# LEDMiniCube_AAmp.net
KiCad netlist of a schematic drawn in Altium Designer
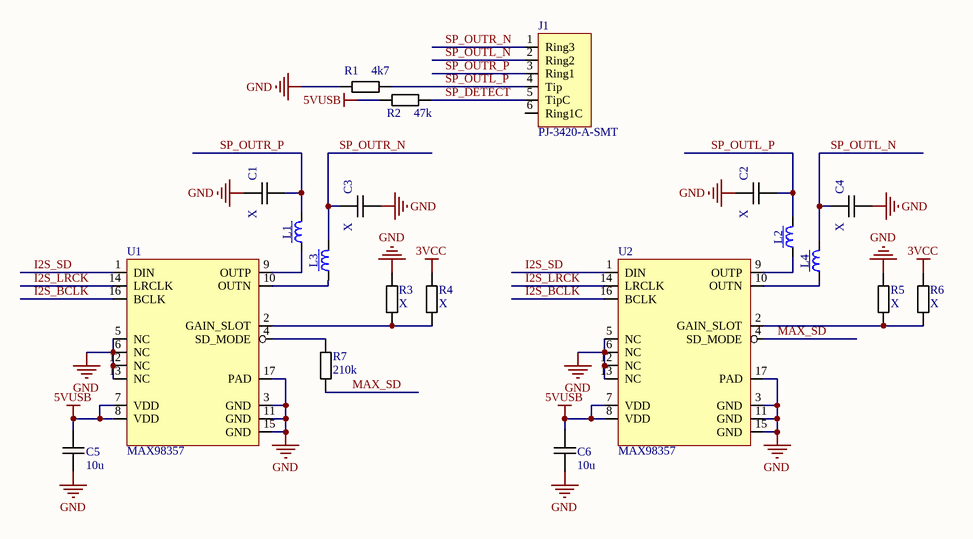
[diagram p0: LEDMiniCube_AAmp.SchDoc]

(export (version "E")
  (design (tool "Eeschema 10.0.6"))
  (components
    (comp (ref "C1") (value "X") (footprint "CAPC2012L") (libsource (lib "BMFT_lib") (part "Capacitor")))
    (comp (ref "C2") (value "X") (footprint "CAPC2012L") (libsource (lib "BMFT_lib") (part "Capacitor")))
    (comp (ref "C3") (value "X") (footprint "CAPC2012L") (libsource (lib "BMFT_lib") (part "Capacitor")))
    (comp (ref "C4") (value "X") (footprint "CAPC2012L") (libsource (lib "BMFT_lib") (part "Capacitor")))
    (comp (ref "C5") (value "10u") (footprint "CAPC2012L") (libsource (lib "BMFT_lib") (part "Capacitor")))
    (comp (ref "C6") (value "10u") (footprint "CAPC2012L") (libsource (lib "BMFT_lib") (part "Capacitor")))
    (comp (ref "J1")
      (value "PJ-3420-A-SMT")
      (footprint "PJ-3420-A-SMT")
      (libsource (lib "BMFT_lib") (part "3.5 socket PJ-3420-A-SMT"))
    )
    (comp (ref "L1")
      (value "~")
      (footprint "INDC2012L")
      (description "Inductor With Core")
      (fields (field (name "AUTHOR") "CERN DEM JLC"))
      (libsource (lib "Inductors & Transformers") (part "Inductor With Magnetic core"))
    )
    (comp (ref "L2")
      (value "~")
      (footprint "INDC2012L")
      (description "Inductor With Core")
      (fields (field (name "AUTHOR") "CERN DEM JLC"))
      (libsource (lib "Inductors & Transformers") (part "Inductor With Magnetic core"))
    )
    (comp (ref "L3")
      (value "~")
      (footprint "INDC2012L")
      (description "Inductor With Core")
      (fields (field (name "AUTHOR") "CERN DEM JLC"))
      (libsource (lib "Inductors & Transformers") (part "Inductor With Magnetic core"))
    )
    (comp (ref "L4")
      (value "~")
      (footprint "INDC2012L")
      (description "Inductor With Core")
      (fields (field (name "AUTHOR") "CERN DEM JLC"))
      (libsource (lib "Inductors & Transformers") (part "Inductor With Magnetic core"))
    )
    (comp (ref "R1") (value "4k7") (footprint "RESC1608L") (libsource (lib "BMFT_lib") (part "Resistor")))
    (comp (ref "R2") (value "47k") (footprint "RESC1608L") (libsource (lib "BMFT_lib") (part "Resistor")))
    (comp (ref "R3") (value "X") (footprint "RESC1608L") (libsource (lib "BMFT_lib") (part "Resistor")))
    (comp (ref "R4") (value "X") (footprint "RESC1608L") (libsource (lib "BMFT_lib") (part "Resistor")))
    (comp (ref "R5") (value "X") (footprint "RESC1608L") (libsource (lib "BMFT_lib") (part "Resistor")))
    (comp (ref "R6") (value "X") (footprint "RESC1608L") (libsource (lib "BMFT_lib") (part "Resistor")))
    (comp (ref "R7") (value "210k") (footprint "RESC1608L") (libsource (lib "BMFT_lib") (part "Resistor")))
    (comp (ref "U1")
      (value "MAX98357")
      (footprint "PQFN50P300X300X80_HS-17N")
      (fields (field (name "PART") "MAX98357A"))
      (libsource (lib "BMFT_lib") (part "MAX98357"))
    )
    (comp (ref "U2")
      (value "MAX98357")
      (footprint "PQFN50P300X300X80_HS-17N")
      (fields (field (name "PART") "MAX98357A"))
      (libsource (lib "BMFT_lib") (part "MAX98357"))
    )
  )
  (nets
    (net (code "1") (name "/I2S_BCLK") (class "Default")
      (node (ref "U1") (pin "16") (pinfunction "BCLK_16") (pintype "passive"))
      (node (ref "U2") (pin "16") (pinfunction "BCLK_16") (pintype "passive"))
    )
    (net (code "2") (name "/I2S_LRCK") (class "Default")
      (node (ref "U1") (pin "14") (pinfunction "LRCLK_14") (pintype "passive"))
      (node (ref "U2") (pin "14") (pinfunction "LRCLK_14") (pintype "passive"))
    )
    (net (code "3") (name "/I2S_SD") (class "Default")
      (node (ref "U1") (pin "1") (pinfunction "DIN_1") (pintype "passive"))
      (node (ref "U2") (pin "1") (pinfunction "DIN_1") (pintype "passive"))
    )
    (net (code "4") (name "/MAX_SD") (class "Default")
      (node (ref "R7") (pin "2") (pintype "passive"))
      (node (ref "U2") (pin "4") (pinfunction "SD_MODE_4") (pintype "passive"))
    )
    (net (code "5") (name "/SP_DETECT") (class "Default")
      (node (ref "J1") (pin "5") (pinfunction "TipC_5") (pintype "passive"))
      (node (ref "R2") (pin "2") (pintype "passive"))
    )
    (net (code "6") (name "/SP_OUTL_N") (class "Default")
      (node (ref "C4") (pin "1") (pintype "passive"))
      (node (ref "J1") (pin "2") (pinfunction "Ring2_2") (pintype "passive"))
      (node (ref "L4") (pin "2") (pinfunction "2_2") (pintype "passive"))
    )
    (net (code "7") (name "/SP_OUTL_P") (class "Default")
      (node (ref "C2") (pin "2") (pintype "passive"))
      (node (ref "J1") (pin "4") (pinfunction "Tip_4") (pintype "passive"))
      (node (ref "L2") (pin "2") (pinfunction "2_2") (pintype "passive"))
      (node (ref "R1") (pin "2") (pintype "passive"))
    )
    (net (code "8") (name "/SP_OUTR_N") (class "Default")
      (node (ref "C3") (pin "1") (pintype "passive"))
      (node (ref "J1") (pin "1") (pinfunction "Ring3_1") (pintype "passive"))
      (node (ref "L3") (pin "2") (pinfunction "2_2") (pintype "passive"))
    )
    (net (code "9") (name "/SP_OUTR_P") (class "Default")
      (node (ref "C1") (pin "2") (pintype "passive"))
      (node (ref "J1") (pin "3") (pinfunction "Ring1_3") (pintype "passive"))
      (node (ref "L1") (pin "2") (pinfunction "2_2") (pintype "passive"))
    )
    (net (code "10") (name "3VCC") (class "Default")
      (node (ref "R4") (pin "2") (pintype "passive"))
      (node (ref "R6") (pin "2") (pintype "passive"))
    )
    (net (code "11") (name "5VUSB") (class "Default")
      (node (ref "C5") (pin "2") (pintype "passive"))
      (node (ref "C6") (pin "2") (pintype "passive"))
      (node (ref "R2") (pin "1") (pintype "passive"))
      (node (ref "U1") (pin "7") (pinfunction "VDD_7") (pintype "passive"))
      (node (ref "U1") (pin "8") (pinfunction "VDD_8") (pintype "passive"))
      (node (ref "U2") (pin "7") (pinfunction "VDD_7") (pintype "passive"))
      (node (ref "U2") (pin "8") (pinfunction "VDD_8") (pintype "passive"))
    )
    (net (code "12") (name "GND") (class "Default")
      (node (ref "C1") (pin "1") (pintype "passive"))
      (node (ref "C2") (pin "1") (pintype "passive"))
      (node (ref "C3") (pin "2") (pintype "passive"))
      (node (ref "C4") (pin "2") (pintype "passive"))
      (node (ref "C5") (pin "1") (pintype "passive"))
      (node (ref "C6") (pin "1") (pintype "passive"))
      (node (ref "R1") (pin "1") (pintype "passive"))
      (node (ref "R3") (pin "2") (pintype "passive"))
      (node (ref "R5") (pin "2") (pintype "passive"))
      (node (ref "U1") (pin "11") (pinfunction "GND_11") (pintype "passive"))
      (node (ref "U1") (pin "12") (pinfunction "NC_12") (pintype "passive"))
      (node (ref "U1") (pin "13") (pinfunction "NC_13") (pintype "passive"))
      (node (ref "U1") (pin "15") (pinfunction "GND_15") (pintype "passive"))
      (node (ref "U1") (pin "17") (pinfunction "PAD_17") (pintype "passive"))
      (node (ref "U1") (pin "3") (pinfunction "GND_3") (pintype "passive"))
      (node (ref "U1") (pin "5") (pinfunction "NC_5") (pintype "passive"))
      (node (ref "U1") (pin "6") (pinfunction "NC_6") (pintype "passive"))
      (node (ref "U2") (pin "11") (pinfunction "GND_11") (pintype "passive"))
      (node (ref "U2") (pin "12") (pinfunction "NC_12") (pintype "passive"))
      (node (ref "U2") (pin "13") (pinfunction "NC_13") (pintype "passive"))
      (node (ref "U2") (pin "15") (pinfunction "GND_15") (pintype "passive"))
      (node (ref "U2") (pin "17") (pinfunction "PAD_17") (pintype "passive"))
      (node (ref "U2") (pin "3") (pinfunction "GND_3") (pintype "passive"))
      (node (ref "U2") (pin "5") (pinfunction "NC_5") (pintype "passive"))
      (node (ref "U2") (pin "6") (pinfunction "NC_6") (pintype "passive"))
    )
    (net (code "13") (name "Net-(U1-GAIN_SLOT)") (class "Default")
      (node (ref "R3") (pin "1") (pintype "passive"))
      (node (ref "R4") (pin "1") (pintype "passive"))
      (node (ref "U1") (pin "2") (pinfunction "GAIN_SLOT_2") (pintype "passive"))
    )
    (net (code "14") (name "Net-(U1-OUTN)") (class "Default")
      (node (ref "L3") (pin "1") (pinfunction "1_1") (pintype "passive"))
      (node (ref "U1") (pin "10") (pinfunction "OUTN_10") (pintype "passive"))
    )
    (net (code "15") (name "Net-(U1-OUTP)") (class "Default")
      (node (ref "L1") (pin "1") (pinfunction "1_1") (pintype "passive"))
      (node (ref "U1") (pin "9") (pinfunction "OUTP_9") (pintype "passive"))
    )
    (net (code "16") (name "Net-(U1-SD_MODE)") (class "Default")
      (node (ref "R7") (pin "1") (pintype "passive"))
      (node (ref "U1") (pin "4") (pinfunction "SD_MODE_4") (pintype "passive"))
    )
    (net (code "17") (name "Net-(U2-GAIN_SLOT)") (class "Default")
      (node (ref "R5") (pin "1") (pintype "passive"))
      (node (ref "R6") (pin "1") (pintype "passive"))
      (node (ref "U2") (pin "2") (pinfunction "GAIN_SLOT_2") (pintype "passive"))
    )
    (net (code "18") (name "Net-(U2-OUTN)") (class "Default")
      (node (ref "L4") (pin "1") (pinfunction "1_1") (pintype "passive"))
      (node (ref "U2") (pin "10") (pinfunction "OUTN_10") (pintype "passive"))
    )
    (net (code "19") (name "Net-(U2-OUTP)") (class "Default")
      (node (ref "L2") (pin "1") (pinfunction "1_1") (pintype "passive"))
      (node (ref "U2") (pin "9") (pinfunction "OUTP_9") (pintype "passive"))
    )
    (net (code "20") (name "unconnected-(J1-Ring1C-Pad6)") (class "Default")
      (node (ref "J1") (pin "6") (pinfunction "Ring1C_6") (pintype "passive"))
    )
  )
)
